# Main_board.net
KiCad netlist of a schematic drawn in Altium Designer
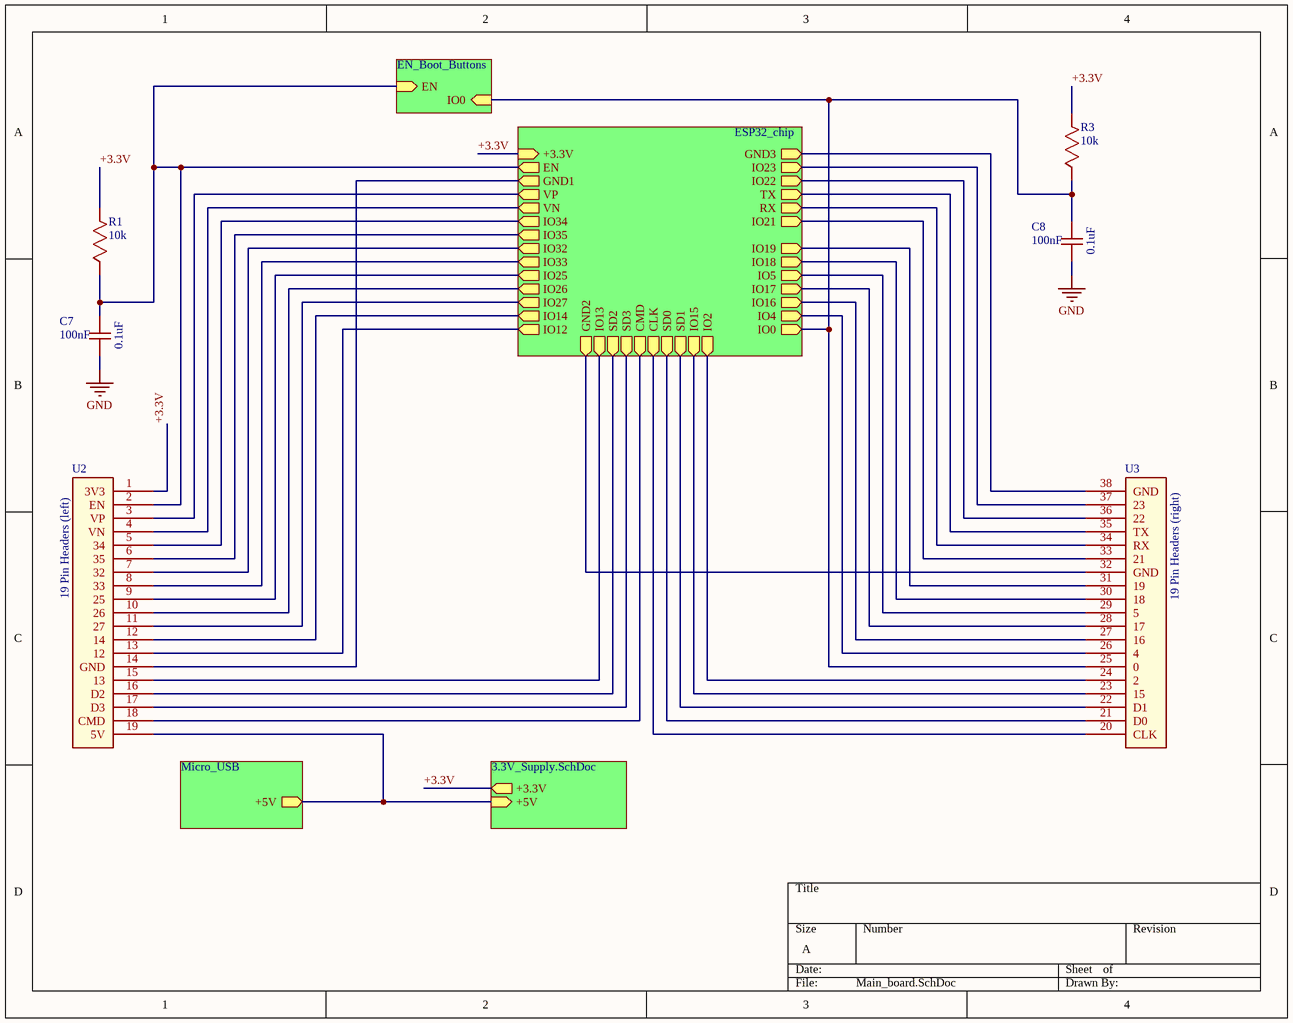
[diagram p0: Main_board.SchDoc]

(export (version "E")
  (design (tool "Eeschema 10.0.6"))
  (components
    (comp (ref "C7")
      (value "100nF")
      (footprint "CAPC2013X140X45ML15T25")
      (description "Ceramic Capacitor, Ceramic, 25V, 10% +Tol, 10% -Tol, X7R, 15% TC, 0.1uF, Surface Mount, 0805")
      (fields
        (field (name "MANUFACTURER") "Murata")
        (field (name "MANUFACTURER PART NUMBER") "GCM21BR71E104KA37L")
      )
      (libsource (lib "ESP32") (part "GCM21BR71E104KA37L"))
    )
    (comp (ref "C8")
      (value "100nF")
      (footprint "CAPC2013X140X45ML15T25")
      (description "Ceramic Capacitor, Ceramic, 25V, 10% +Tol, 10% -Tol, X7R, 15% TC, 0.1uF, Surface Mount, 0805")
      (fields
        (field (name "MANUFACTURER") "Murata")
        (field (name "MANUFACTURER PART NUMBER") "GCM21BR71E104KA37L")
      )
      (libsource (lib "ESP32") (part "GCM21BR71E104KA37L"))
    )
    (comp (ref "R1")
      (value "10k")
      (footprint "FP-CRGCQ0805-IPC_A")
      (description "Res Thick Film 0805 10K Ohm 5% 0.125W(1/8W) ±100ppm/C Pad SMD Automotive T/R")
      (fields
        (field (name "MANUFACTURER") "TE Connectivity")
        (field (name "MANUFACTURER PART NUMBER") "CRGCQ0805J10K")
      )
      (libsource (lib "ESP32") (part "CRGCQ0805J10K"))
    )
    (comp (ref "R3")
      (value "10k")
      (footprint "FP-CRGCQ0805-IPC_A")
      (description "Res Thick Film 0805 10K Ohm 5% 0.125W(1/8W) ±100ppm/C Pad SMD Automotive T/R")
      (fields
        (field (name "MANUFACTURER") "TE Connectivity")
        (field (name "MANUFACTURER PART NUMBER") "CRGCQ0805J10K")
      )
      (libsource (lib "ESP32") (part "CRGCQ0805J10K"))
    )
    (comp (ref "U2")
      (value "19 Pin Headers (left)")
      (footprint "19 Pin headers")
      (libsource (lib "ESP32") (part "19 Pin Headers (left)"))
    )
    (comp (ref "U3")
      (value "19 Pin Headers (right)")
      (footprint "19 Pin headers")
      (libsource (lib "ESP32") (part "19 Pin Headers (right)"))
    )
  )
  (nets
    (net (code "1") (name "/+3.3V") (class "Default")
      (node (ref "R1") (pin "2") (pinfunction "2_2") (pintype "passive"))
      (node (ref "R3") (pin "2") (pinfunction "2_2") (pintype "passive"))
      (node (ref "U2") (pin "1") (pinfunction "3V3_1") (pintype "passive"))
    )
    (net (code "2") (name "/+5V") (class "Default")
      (node (ref "U2") (pin "19") (pinfunction "5V_19") (pintype "passive"))
    )
    (net (code "3") (name "/CLK") (class "Default")
      (node (ref "U3") (pin "20") (pinfunction "CLK_20") (pintype "passive"))
    )
    (net (code "4") (name "/CMD") (class "Default")
      (node (ref "U2") (pin "18") (pinfunction "CMD_18") (pintype "passive"))
    )
    (net (code "5") (name "/EN") (class "Default")
      (node (ref "C7") (pin "2") (pinfunction "2_2") (pintype "passive"))
      (node (ref "R1") (pin "1") (pinfunction "1_1") (pintype "passive"))
      (node (ref "U2") (pin "2") (pinfunction "EN_2") (pintype "passive"))
    )
    (net (code "6") (name "/GND1") (class "Default")
      (node (ref "U2") (pin "14") (pinfunction "GND_14") (pintype "passive"))
    )
    (net (code "7") (name "/GND2") (class "Default")
      (node (ref "U3") (pin "32") (pinfunction "GND_32") (pintype "passive"))
    )
    (net (code "8") (name "/GND3") (class "Default")
      (node (ref "U3") (pin "38") (pinfunction "GND_38") (pintype "passive"))
    )
    (net (code "9") (name "/IO0") (class "Default")
      (node (ref "C8") (pin "2") (pinfunction "2_2") (pintype "passive"))
      (node (ref "R3") (pin "1") (pinfunction "1_1") (pintype "passive"))
      (node (ref "U3") (pin "25") (pinfunction "0_25") (pintype "passive"))
    )
    (net (code "10") (name "/IO2") (class "Default")
      (node (ref "U3") (pin "24") (pinfunction "2_24") (pintype "passive"))
    )
    (net (code "11") (name "/IO4") (class "Default")
      (node (ref "U3") (pin "26") (pinfunction "4_26") (pintype "passive"))
    )
    (net (code "12") (name "/IO5") (class "Default")
      (node (ref "U3") (pin "29") (pinfunction "5_29") (pintype "passive"))
    )
    (net (code "13") (name "/IO12") (class "Default")
      (node (ref "U2") (pin "13") (pinfunction "12_13") (pintype "passive"))
    )
    (net (code "14") (name "/IO13") (class "Default")
      (node (ref "U2") (pin "15") (pinfunction "13_15") (pintype "passive"))
    )
    (net (code "15") (name "/IO14") (class "Default")
      (node (ref "U2") (pin "12") (pinfunction "14_12") (pintype "passive"))
    )
    (net (code "16") (name "/IO15") (class "Default")
      (node (ref "U3") (pin "23") (pinfunction "15_23") (pintype "passive"))
    )
    (net (code "17") (name "/IO16") (class "Default")
      (node (ref "U3") (pin "27") (pinfunction "16_27") (pintype "passive"))
    )
    (net (code "18") (name "/IO17") (class "Default")
      (node (ref "U3") (pin "28") (pinfunction "17_28") (pintype "passive"))
    )
    (net (code "19") (name "/IO18") (class "Default")
      (node (ref "U3") (pin "30") (pinfunction "18_30") (pintype "passive"))
    )
    (net (code "20") (name "/IO19") (class "Default")
      (node (ref "U3") (pin "31") (pinfunction "19_31") (pintype "passive"))
    )
    (net (code "21") (name "/IO21") (class "Default")
      (node (ref "U3") (pin "33") (pinfunction "21_33") (pintype "passive"))
    )
    (net (code "22") (name "/IO22") (class "Default")
      (node (ref "U3") (pin "36") (pinfunction "22_36") (pintype "passive"))
    )
    (net (code "23") (name "/IO23") (class "Default")
      (node (ref "U3") (pin "37") (pinfunction "23_37") (pintype "passive"))
    )
    (net (code "24") (name "/IO25") (class "Default")
      (node (ref "U2") (pin "9") (pinfunction "25_9") (pintype "passive"))
    )
    (net (code "25") (name "/IO26") (class "Default")
      (node (ref "U2") (pin "10") (pinfunction "26_10") (pintype "passive"))
    )
    (net (code "26") (name "/IO27") (class "Default")
      (node (ref "U2") (pin "11") (pinfunction "27_11") (pintype "passive"))
    )
    (net (code "27") (name "/IO32") (class "Default")
      (node (ref "U2") (pin "7") (pinfunction "32_7") (pintype "passive"))
    )
    (net (code "28") (name "/IO33") (class "Default")
      (node (ref "U2") (pin "8") (pinfunction "33_8") (pintype "passive"))
    )
    (net (code "29") (name "/IO34") (class "Default")
      (node (ref "U2") (pin "5") (pinfunction "34_5") (pintype "passive"))
    )
    (net (code "30") (name "/IO35") (class "Default")
      (node (ref "U2") (pin "6") (pinfunction "35_6") (pintype "passive"))
    )
    (net (code "31") (name "/RX") (class "Default")
      (node (ref "U3") (pin "34") (pinfunction "RX_34") (pintype "passive"))
    )
    (net (code "32") (name "/SD0") (class "Default")
      (node (ref "U3") (pin "21") (pinfunction "D0_21") (pintype "passive"))
    )
    (net (code "33") (name "/SD1") (class "Default")
      (node (ref "U3") (pin "22") (pinfunction "D1_22") (pintype "passive"))
    )
    (net (code "34") (name "/SD2") (class "Default")
      (node (ref "U2") (pin "16") (pinfunction "D2_16") (pintype "passive"))
    )
    (net (code "35") (name "/SD3") (class "Default")
      (node (ref "U2") (pin "17") (pinfunction "D3_17") (pintype "passive"))
    )
    (net (code "36") (name "/TX") (class "Default")
      (node (ref "U3") (pin "35") (pinfunction "TX_35") (pintype "passive"))
    )
    (net (code "37") (name "/VN") (class "Default")
      (node (ref "U2") (pin "4") (pinfunction "VN_4") (pintype "passive"))
    )
    (net (code "38") (name "/VP") (class "Default")
      (node (ref "U2") (pin "3") (pinfunction "VP_3") (pintype "passive"))
    )
    (net (code "39") (name "GND") (class "Default")
      (node (ref "C7") (pin "1") (pinfunction "1_1") (pintype "passive"))
      (node (ref "C8") (pin "1") (pinfunction "1_1") (pintype "passive"))
    )
  )
)
